# ArtixBank34.net
KiCad netlist of a schematic drawn in Altium Designer
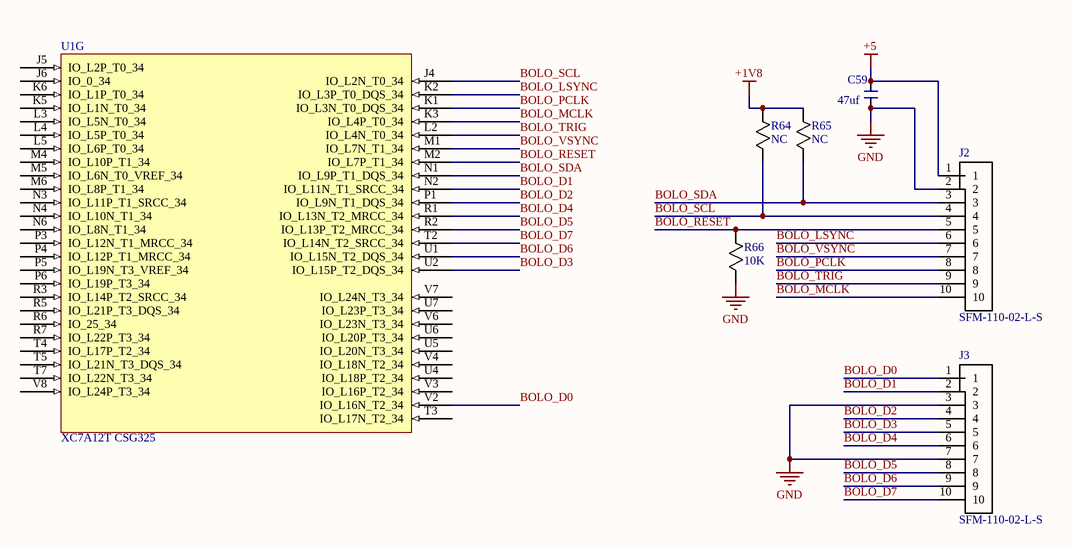
[diagram p0: ArtixBank34.SchDoc]

(export (version "E")
  (design (tool "Eeschema 10.0.6"))
  (components
    (comp (ref "C59")
      (value "47uf")
      (footprint "0805FOOTPRINT")
      (description "0805")
      (libsource (lib "Capacitors") (part "47uf_0805"))
    )
    (comp (ref "J2")
      (value "SFM-110-02-L-S")
      (footprint "SFM-110-02-L-S")
      (libsource (lib "Connectors") (part "SFM-110-02-L-S"))
    )
    (comp (ref "J3")
      (value "SFM-110-02-L-S")
      (footprint "SFM-110-02-L-S")
      (libsource (lib "Connectors") (part "SFM-110-02-L-S"))
    )
    (comp (ref "R64") (value "NC") (footprint "RES_CRCW_0402") (libsource (lib "Resistors") (part "NC_0402")))
    (comp (ref "R65") (value "NC") (footprint "RES_CRCW_0402") (libsource (lib "Resistors") (part "NC_0402")))
    (comp (ref "R66")
      (value "10K")
      (footprint "RES_CRCW_0402")
      (description "0402")
      (fields (field (name "TOLERANCE") "1%"))
      (libsource (lib "Resistors") (part "10K_0402"))
    )
    (comp (ref "U1")
      (value "XC7A12T CSG325")
      (footprint "BGA324C80P18X18_1500X1500X150")
      (libsource (lib "XC7A12T_1CPG238I") (part "XC7A12T_1CSG325I"))
    )
  )
  (nets
    (net (code "1") (name "+1V8") (class "Default")
      (node (ref "R64") (pin "1") (pinfunction "1_1") (pintype "passive"))
      (node (ref "R65") (pin "1") (pinfunction "1_1") (pintype "passive"))
    )
    (net (code "2") (name "+5") (class "Default")
      (node (ref "C59") (pin "1") (pinfunction "1_1") (pintype "passive"))
      (node (ref "J2") (pin "1") (pinfunction "1_1") (pintype "passive"))
    )
    (net (code "3") (name "/BOLO_D0") (class "Default")
      (node (ref "J3") (pin "1") (pinfunction "1_1") (pintype "passive"))
      (node (ref "U1") (pin "V2") (pinfunction "IO_L16N_T2_34_V2") (pintype "input"))
    )
    (net (code "4") (name "/BOLO_D1") (class "Default")
      (node (ref "J3") (pin "2") (pinfunction "2_2") (pintype "passive"))
      (node (ref "U1") (pin "N2") (pinfunction "IO_L11N_T1_SRCC_34_N2") (pintype "input"))
    )
    (net (code "5") (name "/BOLO_D2") (class "Default")
      (node (ref "J3") (pin "4") (pinfunction "4_4") (pintype "passive"))
      (node (ref "U1") (pin "P1") (pinfunction "IO_L9N_T1_DQS_34_P1") (pintype "input"))
    )
    (net (code "6") (name "/BOLO_D3") (class "Default")
      (node (ref "J3") (pin "5") (pinfunction "5_5") (pintype "passive"))
      (node (ref "U1") (pin "U2") (pinfunction "IO_L15P_T2_DQS_34_U2") (pintype "input"))
    )
    (net (code "7") (name "/BOLO_D4") (class "Default")
      (node (ref "J3") (pin "6") (pinfunction "6_6") (pintype "passive"))
      (node (ref "U1") (pin "R1") (pinfunction "IO_L13N_T2_MRCC_34_R1") (pintype "input"))
    )
    (net (code "8") (name "/BOLO_D5") (class "Default")
      (node (ref "J3") (pin "8") (pinfunction "8_8") (pintype "passive"))
      (node (ref "U1") (pin "R2") (pinfunction "IO_L13P_T2_MRCC_34_R2") (pintype "input"))
    )
    (net (code "9") (name "/BOLO_D6") (class "Default")
      (node (ref "J3") (pin "9") (pinfunction "9_9") (pintype "passive"))
      (node (ref "U1") (pin "U1") (pinfunction "IO_L15N_T2_DQS_34_U1") (pintype "input"))
    )
    (net (code "10") (name "/BOLO_D7") (class "Default")
      (node (ref "J3") (pin "10") (pinfunction "10_10") (pintype "passive"))
      (node (ref "U1") (pin "T2") (pinfunction "IO_L14N_T2_SRCC_34_T2") (pintype "input"))
    )
    (net (code "11") (name "/BOLO_LSYNC") (class "Default")
      (node (ref "J2") (pin "6") (pinfunction "6_6") (pintype "passive"))
      (node (ref "U1") (pin "K2") (pinfunction "IO_L3P_T0_DQS_34_K2") (pintype "input"))
    )
    (net (code "12") (name "/BOLO_MCLK") (class "Default")
      (node (ref "J2") (pin "10") (pinfunction "10_10") (pintype "passive"))
      (node (ref "U1") (pin "K3") (pinfunction "IO_L4P_T0_34_K3") (pintype "input"))
    )
    (net (code "13") (name "/BOLO_PCLK") (class "Default")
      (node (ref "J2") (pin "8") (pinfunction "8_8") (pintype "passive"))
      (node (ref "U1") (pin "K1") (pinfunction "IO_L3N_T0_DQS_34_K1") (pintype "input"))
    )
    (net (code "14") (name "/BOLO_RESET") (class "Default")
      (node (ref "J2") (pin "5") (pinfunction "5_5") (pintype "passive"))
      (node (ref "R66") (pin "1") (pinfunction "1_1") (pintype "passive"))
      (node (ref "U1") (pin "M2") (pinfunction "IO_L7P_T1_34_M2") (pintype "input"))
    )
    (net (code "15") (name "/BOLO_SCL") (class "Default")
      (node (ref "J2") (pin "4") (pinfunction "4_4") (pintype "passive"))
      (node (ref "R64") (pin "2") (pinfunction "2_2") (pintype "passive"))
      (node (ref "U1") (pin "J4") (pinfunction "IO_L2N_T0_34_J4") (pintype "input"))
    )
    (net (code "16") (name "/BOLO_SDA") (class "Default")
      (node (ref "J2") (pin "3") (pinfunction "3_3") (pintype "passive"))
      (node (ref "R65") (pin "2") (pinfunction "2_2") (pintype "passive"))
      (node (ref "U1") (pin "N1") (pinfunction "IO_L9P_T1_DQS_34_N1") (pintype "input"))
    )
    (net (code "17") (name "/BOLO_TRIG") (class "Default")
      (node (ref "J2") (pin "9") (pinfunction "9_9") (pintype "passive"))
      (node (ref "U1") (pin "L2") (pinfunction "IO_L4N_T0_34_L2") (pintype "input"))
    )
    (net (code "18") (name "/BOLO_VSYNC") (class "Default")
      (node (ref "J2") (pin "7") (pinfunction "7_7") (pintype "passive"))
      (node (ref "U1") (pin "M1") (pinfunction "IO_L7N_T1_34_M1") (pintype "input"))
    )
    (net (code "19") (name "GND") (class "Default")
      (node (ref "C59") (pin "2") (pinfunction "2_2") (pintype "passive"))
      (node (ref "J2") (pin "2") (pinfunction "2_2") (pintype "passive"))
      (node (ref "J3") (pin "3") (pinfunction "3_3") (pintype "passive"))
      (node (ref "J3") (pin "7") (pinfunction "7_7") (pintype "passive"))
      (node (ref "R66") (pin "2") (pinfunction "2_2") (pintype "passive"))
    )
    (net (code "20") (name "unconnected-(U1G-IO_0_34-PadJ6)") (class "Default")
      (node (ref "U1") (pin "J6") (pinfunction "IO_0_34_J6") (pintype "input"))
    )
    (net (code "21") (name "unconnected-(U1G-IO_25_34-PadR6)") (class "Default")
      (node (ref "U1") (pin "R6") (pinfunction "IO_25_34_R6") (pintype "input"))
    )
    (net (code "22") (name "unconnected-(U1G-IO_L1N_T0_34-PadK5)") (class "Default")
      (node (ref "U1") (pin "K5") (pinfunction "IO_L1N_T0_34_K5") (pintype "input"))
    )
    (net (code "23") (name "unconnected-(U1G-IO_L1P_T0_34-PadK6)") (class "Default")
      (node (ref "U1") (pin "K6") (pinfunction "IO_L1P_T0_34_K6") (pintype "input"))
    )
    (net (code "24") (name "unconnected-(U1G-IO_L2P_T0_34-PadJ5)") (class "Default")
      (node (ref "U1") (pin "J5") (pinfunction "IO_L2P_T0_34_J5") (pintype "input"))
    )
    (net (code "25") (name "unconnected-(U1G-IO_L5N_T0_34-PadL3)") (class "Default")
      (node (ref "U1") (pin "L3") (pinfunction "IO_L5N_T0_34_L3") (pintype "input"))
    )
    (net (code "26") (name "unconnected-(U1G-IO_L5P_T0_34-PadL4)") (class "Default")
      (node (ref "U1") (pin "L4") (pinfunction "IO_L5P_T0_34_L4") (pintype "input"))
    )
    (net (code "27") (name "unconnected-(U1G-IO_L6N_T0_VREF_34-PadM5)") (class "Default")
      (node (ref "U1") (pin "M5") (pinfunction "IO_L6N_T0_VREF_34_M5") (pintype "input"))
    )
    (net (code "28") (name "unconnected-(U1G-IO_L6P_T0_34-PadL5)") (class "Default")
      (node (ref "U1") (pin "L5") (pinfunction "IO_L6P_T0_34_L5") (pintype "input"))
    )
    (net (code "29") (name "unconnected-(U1G-IO_L8N_T1_34-PadN6)") (class "Default")
      (node (ref "U1") (pin "N6") (pinfunction "IO_L8N_T1_34_N6") (pintype "input"))
    )
    (net (code "30") (name "unconnected-(U1G-IO_L8P_T1_34-PadM6)") (class "Default")
      (node (ref "U1") (pin "M6") (pinfunction "IO_L8P_T1_34_M6") (pintype "input"))
    )
    (net (code "31") (name "unconnected-(U1G-IO_L10N_T1_34-PadN4)") (class "Default")
      (node (ref "U1") (pin "N4") (pinfunction "IO_L10N_T1_34_N4") (pintype "input"))
    )
    (net (code "32") (name "unconnected-(U1G-IO_L10P_T1_34-PadM4)") (class "Default")
      (node (ref "U1") (pin "M4") (pinfunction "IO_L10P_T1_34_M4") (pintype "input"))
    )
    (net (code "33") (name "unconnected-(U1G-IO_L11P_T1_SRCC_34-PadN3)") (class "Default")
      (node (ref "U1") (pin "N3") (pinfunction "IO_L11P_T1_SRCC_34_N3") (pintype "input"))
    )
    (net (code "34") (name "unconnected-(U1G-IO_L12N_T1_MRCC_34-PadP3)") (class "Default")
      (node (ref "U1") (pin "P3") (pinfunction "IO_L12N_T1_MRCC_34_P3") (pintype "input"))
    )
    (net (code "35") (name "unconnected-(U1G-IO_L12P_T1_MRCC_34-PadP4)") (class "Default")
      (node (ref "U1") (pin "P4") (pinfunction "IO_L12P_T1_MRCC_34_P4") (pintype "input"))
    )
    (net (code "36") (name "unconnected-(U1G-IO_L14P_T2_SRCC_34-PadR3)") (class "Default")
      (node (ref "U1") (pin "R3") (pinfunction "IO_L14P_T2_SRCC_34_R3") (pintype "input"))
    )
    (net (code "37") (name "unconnected-(U1G-IO_L16P_T2_34-PadV3)") (class "Default")
      (node (ref "U1") (pin "V3") (pinfunction "IO_L16P_T2_34_V3") (pintype "input"))
    )
    (net (code "38") (name "unconnected-(U1G-IO_L17N_T2_34-PadT3)") (class "Default")
      (node (ref "U1") (pin "T3") (pinfunction "IO_L17N_T2_34_T3") (pintype "input"))
    )
    (net (code "39") (name "unconnected-(U1G-IO_L17P_T2_34-PadT4)") (class "Default")
      (node (ref "U1") (pin "T4") (pinfunction "IO_L17P_T2_34_T4") (pintype "input"))
    )
    (net (code "40") (name "unconnected-(U1G-IO_L18N_T2_34-PadV4)") (class "Default")
      (node (ref "U1") (pin "V4") (pinfunction "IO_L18N_T2_34_V4") (pintype "input"))
    )
    (net (code "41") (name "unconnected-(U1G-IO_L18P_T2_34-PadU4)") (class "Default")
      (node (ref "U1") (pin "U4") (pinfunction "IO_L18P_T2_34_U4") (pintype "input"))
    )
    (net (code "42") (name "unconnected-(U1G-IO_L19N_T3_VREF_34-PadP5)") (class "Default")
      (node (ref "U1") (pin "P5") (pinfunction "IO_L19N_T3_VREF_34_P5") (pintype "input"))
    )
    (net (code "43") (name "unconnected-(U1G-IO_L19P_T3_34-PadP6)") (class "Default")
      (node (ref "U1") (pin "P6") (pinfunction "IO_L19P_T3_34_P6") (pintype "input"))
    )
    (net (code "44") (name "unconnected-(U1G-IO_L20N_T3_34-PadU5)") (class "Default")
      (node (ref "U1") (pin "U5") (pinfunction "IO_L20N_T3_34_U5") (pintype "input"))
    )
    (net (code "45") (name "unconnected-(U1G-IO_L20P_T3_34-PadU6)") (class "Default")
      (node (ref "U1") (pin "U6") (pinfunction "IO_L20P_T3_34_U6") (pintype "input"))
    )
    (net (code "46") (name "unconnected-(U1G-IO_L21N_T3_DQS_34-PadT5)") (class "Default")
      (node (ref "U1") (pin "T5") (pinfunction "IO_L21N_T3_DQS_34_T5") (pintype "input"))
    )
    (net (code "47") (name "unconnected-(U1G-IO_L21P_T3_DQS_34-PadR5)") (class "Default")
      (node (ref "U1") (pin "R5") (pinfunction "IO_L21P_T3_DQS_34_R5") (pintype "input"))
    )
    (net (code "48") (name "unconnected-(U1G-IO_L22N_T3_34-PadT7)") (class "Default")
      (node (ref "U1") (pin "T7") (pinfunction "IO_L22N_T3_34_T7") (pintype "input"))
    )
    (net (code "49") (name "unconnected-(U1G-IO_L22P_T3_34-PadR7)") (class "Default")
      (node (ref "U1") (pin "R7") (pinfunction "IO_L22P_T3_34_R7") (pintype "input"))
    )
    (net (code "50") (name "unconnected-(U1G-IO_L23N_T3_34-PadV6)") (class "Default")
      (node (ref "U1") (pin "V6") (pinfunction "IO_L23N_T3_34_V6") (pintype "input"))
    )
    (net (code "51") (name "unconnected-(U1G-IO_L23P_T3_34-PadU7)") (class "Default")
      (node (ref "U1") (pin "U7") (pinfunction "IO_L23P_T3_34_U7") (pintype "input"))
    )
    (net (code "52") (name "unconnected-(U1G-IO_L24N_T3_34-PadV7)") (class "Default")
      (node (ref "U1") (pin "V7") (pinfunction "IO_L24N_T3_34_V7") (pintype "input"))
    )
    (net (code "53") (name "unconnected-(U1G-IO_L24P_T3_34-PadV8)") (class "Default")
      (node (ref "U1") (pin "V8") (pinfunction "IO_L24P_T3_34_V8") (pintype "input"))
    )
  )
)
